# Nomorobo85-1.net
KiCad netlist of a schematic drawn in EAGLE
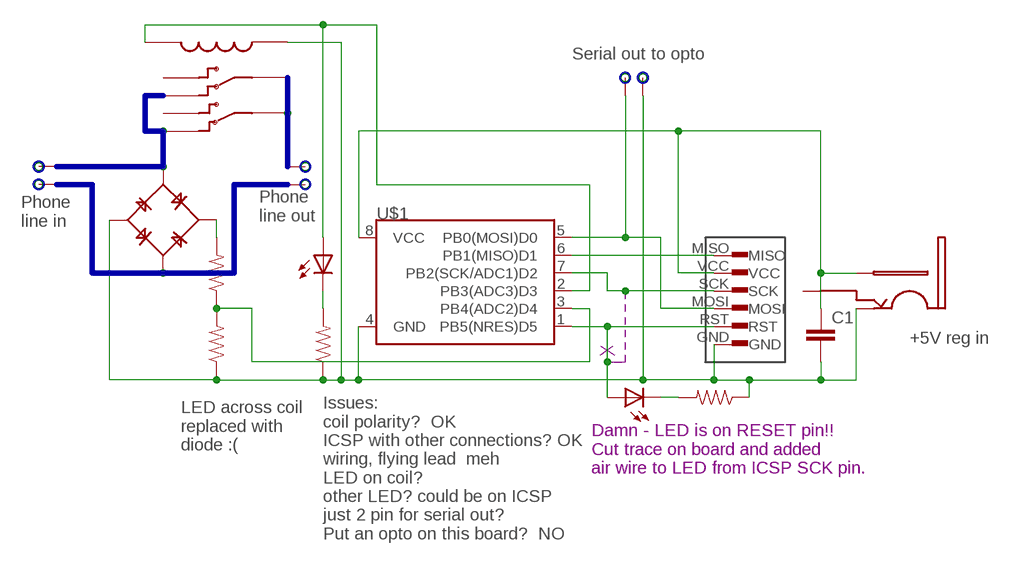
[diagram p0: schematic, sheet 1]

(export (version "E")
  (design (tool "Eeschema 10.0.6"))
  (components
    (comp (ref "C1")
      (value "CAP1206")
      (footprint "eagle-import:1206")
      (libsource (lib "eagle-import") (part "CAP1206"))
    )
    (comp (ref "U$1")
      (value "ATTINY85SO08-I-HAVE-THESE")
      (footprint "eagle-import:SO08-EIAJ")
      (libsource (lib "eagle-import") (part "ATTINY85SO08-I-HAVE-THESE"))
    )
    (comp (ref "U$2")
      (value "RESISTOR1206WW")
      (footprint "eagle-import:1206WW")
      (libsource (lib "eagle-import") (part "RESISTOR1206WW"))
    )
    (comp (ref "U$3")
      (value "RESISTOR1206WW")
      (footprint "eagle-import:1206WW")
      (libsource (lib "eagle-import") (part "RESISTOR1206WW"))
    )
    (comp (ref "U$4")
      (value "RESISTOR1206WW")
      (footprint "eagle-import:1206WW")
      (libsource (lib "eagle-import") (part "RESISTOR1206WW"))
    )
    (comp (ref "U$5")
      (value "BRIDGE-ROUNDMY-600V-1A")
      (footprint "eagle-import:BRIDGE-ROUND")
      (libsource (lib "eagle-import") (part "BRIDGE-ROUNDMY-600V-1A"))
    )
    (comp (ref "U$6")
      (value "M2X3-HEADERICSP-LONGPADS")
      (footprint "eagle-import:M2X3-LONGPADS")
      (libsource (lib "eagle-import") (part "M2X3-HEADERICSP-LONGPADS"))
    )
    (comp (ref "U$7")
      (value "SOLDER-PAD-2LONGPADS")
      (footprint "eagle-import:02P")
      (libsource (lib "eagle-import") (part "SOLDER-PAD-2LONGPADS"))
    )
    (comp (ref "U$8")
      (value "SOLDER-PAD-2LONGPADS")
      (footprint "eagle-import:02P")
      (libsource (lib "eagle-import") (part "SOLDER-PAD-2LONGPADS"))
    )
    (comp (ref "U$9")
      (value "RESISTOR1206WW")
      (footprint "eagle-import:1206WW")
      (libsource (lib "eagle-import") (part "RESISTOR1206WW"))
    )
    (comp (ref "U$10")
      (value "BARREL-COAX-PWR")
      (footprint "eagle-import:BARREL-COAX-CONNECTOR")
      (libsource (lib "eagle-import") (part "BARREL-COAX-PWR"))
    )
    (comp (ref "U$11")
      (value "LED-12061206")
      (footprint "eagle-import:1206W")
      (libsource (lib "eagle-import") (part "LED-12061206"))
    )
    (comp (ref "U$12")
      (value "RELAY-DPDT")
      (footprint "eagle-import:RELAY-DPDT")
      (libsource (lib "eagle-import") (part "RELAY-DPDT"))
    )
    (comp (ref "U$13")
      (value "SOLDER-PAD-2LONGPPAD2")
      (footprint "eagle-import:SOLDER-PAD-2-LONGPADS")
      (libsource (lib "eagle-import") (part "SOLDER-PAD-2LONGPPAD2"))
    )
    (comp (ref "U$14")
      (value "LED-12061206")
      (footprint "eagle-import:1206W")
      (libsource (lib "eagle-import") (part "LED-12061206"))
    )
  )
  (nets
    (net (code "1") (name "Net-(U$1-GND)") (class "Default")
      (node (ref "C1") (pin "2") (pinfunction "2_2") (pintype "passive"))
      (node (ref "U$1") (pin "4") (pinfunction "GND_4") (pintype "bidirectional"))
      (node (ref "U$10") (pin "SHELL") (pinfunction "SHELL_SHELL") (pintype "bidirectional"))
      (node (ref "U$12") (pin "COIL+") (pinfunction "COIL+_COIL+") (pintype "bidirectional"))
      (node (ref "U$13") (pin "P$2") (pinfunction "P$1_P$2") (pintype "bidirectional"))
      (node (ref "U$2") (pin "1") (pinfunction "1_1") (pintype "passive"))
      (node (ref "U$4") (pin "1") (pinfunction "1_1") (pintype "passive"))
      (node (ref "U$5") (pin "OUT-") (pinfunction "V-_OUT-") (pintype "bidirectional"))
      (node (ref "U$6") (pin "GND") (pinfunction "GND_GND") (pintype "bidirectional"))
      (node (ref "U$9") (pin "1") (pinfunction "1_1") (pintype "passive"))
    )
    (net (code "2") (name "Net-(U$1-PB0(MOSI)D0)") (class "Default")
      (node (ref "U$1") (pin "5") (pinfunction "PB0(MOSI)D0_5") (pintype "bidirectional"))
      (node (ref "U$13") (pin "P$3") (pinfunction "P$2_P$3") (pintype "bidirectional"))
      (node (ref "U$6") (pin "MOSI") (pinfunction "MOSI_MOSI") (pintype "bidirectional"))
    )
    (net (code "3") (name "Net-(U$1-PB1(MISO)D1)") (class "Default")
      (node (ref "U$1") (pin "6") (pinfunction "PB1(MISO)D1_6") (pintype "bidirectional"))
      (node (ref "U$6") (pin "MISO") (pinfunction "MISO_MISO") (pintype "bidirectional"))
    )
    (net (code "4") (name "Net-(U$1-PB2(SCK{slash}ADC1)D2)") (class "Default")
      (node (ref "U$1") (pin "7") (pinfunction "PB2(SCK/ADC1)D2_7") (pintype "bidirectional"))
      (node (ref "U$6") (pin "SCK") (pinfunction "SCK_SCK") (pintype "bidirectional"))
    )
    (net (code "5") (name "Net-(U$1-PB3(ADC3)D3)") (class "Default")
      (node (ref "U$1") (pin "2") (pinfunction "PB3(ADC3)D3_2") (pintype "bidirectional"))
      (node (ref "U$11") (pin "1") (pinfunction "A_1") (pintype "passive"))
      (node (ref "U$12") (pin "COIL-") (pinfunction "COIL-_COIL-") (pintype "bidirectional"))
    )
    (net (code "6") (name "Net-(U$1-PB4(ADC2)D4)") (class "Default")
      (node (ref "U$1") (pin "3") (pinfunction "PB4(ADC2)D4_3") (pintype "bidirectional"))
      (node (ref "U$3") (pin "1") (pinfunction "1_1") (pintype "passive"))
      (node (ref "U$4") (pin "2") (pinfunction "2_2") (pintype "passive"))
    )
    (net (code "7") (name "Net-(U$1-PB5(NRES)D5)") (class "Default")
      (node (ref "U$1") (pin "1") (pinfunction "PB5(NRES)D5_1") (pintype "bidirectional"))
      (node (ref "U$14") (pin "1") (pinfunction "A_1") (pintype "passive"))
      (node (ref "U$6") (pin "RST") (pinfunction "RST_RST") (pintype "bidirectional"))
    )
    (net (code "8") (name "Net-(U$1-VCC)") (class "Default")
      (node (ref "C1") (pin "1") (pinfunction "1_1") (pintype "passive"))
      (node (ref "U$1") (pin "8") (pinfunction "VCC_8") (pintype "bidirectional"))
      (node (ref "U$10") (pin "PIN") (pinfunction "PIN_PIN") (pintype "bidirectional"))
      (node (ref "U$6") (pin "VCC") (pinfunction "VCC_VCC") (pintype "bidirectional"))
    )
    (net (code "9") (name "Net-(U$5-IN1)") (class "Default")
      (node (ref "U$12") (pin "NC1") (pinfunction "NC1_NC1") (pintype "bidirectional"))
      (node (ref "U$12") (pin "NC2") (pinfunction "NC2_NC2") (pintype "bidirectional"))
      (node (ref "U$5") (pin "AC1") (pinfunction "IN1_AC1") (pintype "bidirectional"))
      (node (ref "U$7") (pin "1") (pinfunction "P$1_1") (pintype "bidirectional"))
    )
    (net (code "10") (name "Net-(U$5-IN2)") (class "Default")
      (node (ref "U$5") (pin "AC2") (pinfunction "IN2_AC2") (pintype "bidirectional"))
      (node (ref "U$7") (pin "2") (pinfunction "P$2_2") (pintype "bidirectional"))
      (node (ref "U$8") (pin "1") (pinfunction "P$1_1") (pintype "bidirectional"))
    )
    (net (code "11") (name "Net-(U$5-V+)") (class "Default")
      (node (ref "U$3") (pin "2") (pinfunction "2_2") (pintype "passive"))
      (node (ref "U$5") (pin "OUT+") (pinfunction "V+_OUT+") (pintype "bidirectional"))
    )
    (net (code "12") (name "Net-(U$8-P$2)") (class "Default")
      (node (ref "U$12") (pin "COM1") (pinfunction "COM1_COM1") (pintype "bidirectional"))
      (node (ref "U$12") (pin "COM2") (pinfunction "COM2_COM2") (pintype "bidirectional"))
      (node (ref "U$8") (pin "2") (pinfunction "P$2_2") (pintype "bidirectional"))
    )
    (net (code "13") (name "Net-(U$11-C)") (class "Default")
      (node (ref "U$11") (pin "2") (pinfunction "C_2") (pintype "passive"))
      (node (ref "U$9") (pin "2") (pinfunction "2_2") (pintype "passive"))
    )
    (net (code "14") (name "Net-(U$14-C)") (class "Default")
      (node (ref "U$14") (pin "2") (pinfunction "C_2") (pintype "passive"))
      (node (ref "U$2") (pin "2") (pinfunction "2_2") (pintype "passive"))
    )
    (net (code "15") (name "unconnected-(U$10-PadSWITCH)") (class "Default")
      (node (ref "U$10") (pin "SWITCH") (pinfunction "SWITCH_SWITCH") (pintype "bidirectional"))
    )
    (net (code "16") (name "unconnected-(U$12-PadNO1)") (class "Default")
      (node (ref "U$12") (pin "NO1") (pinfunction "NO1_NO1") (pintype "bidirectional"))
    )
    (net (code "17") (name "unconnected-(U$12-PadNO2)") (class "Default")
      (node (ref "U$12") (pin "NO2") (pinfunction "NO2_NO2") (pintype "bidirectional"))
    )
  )
)
